# connector_PCI.net
KiCad netlist of a schematic drawn in EAGLE
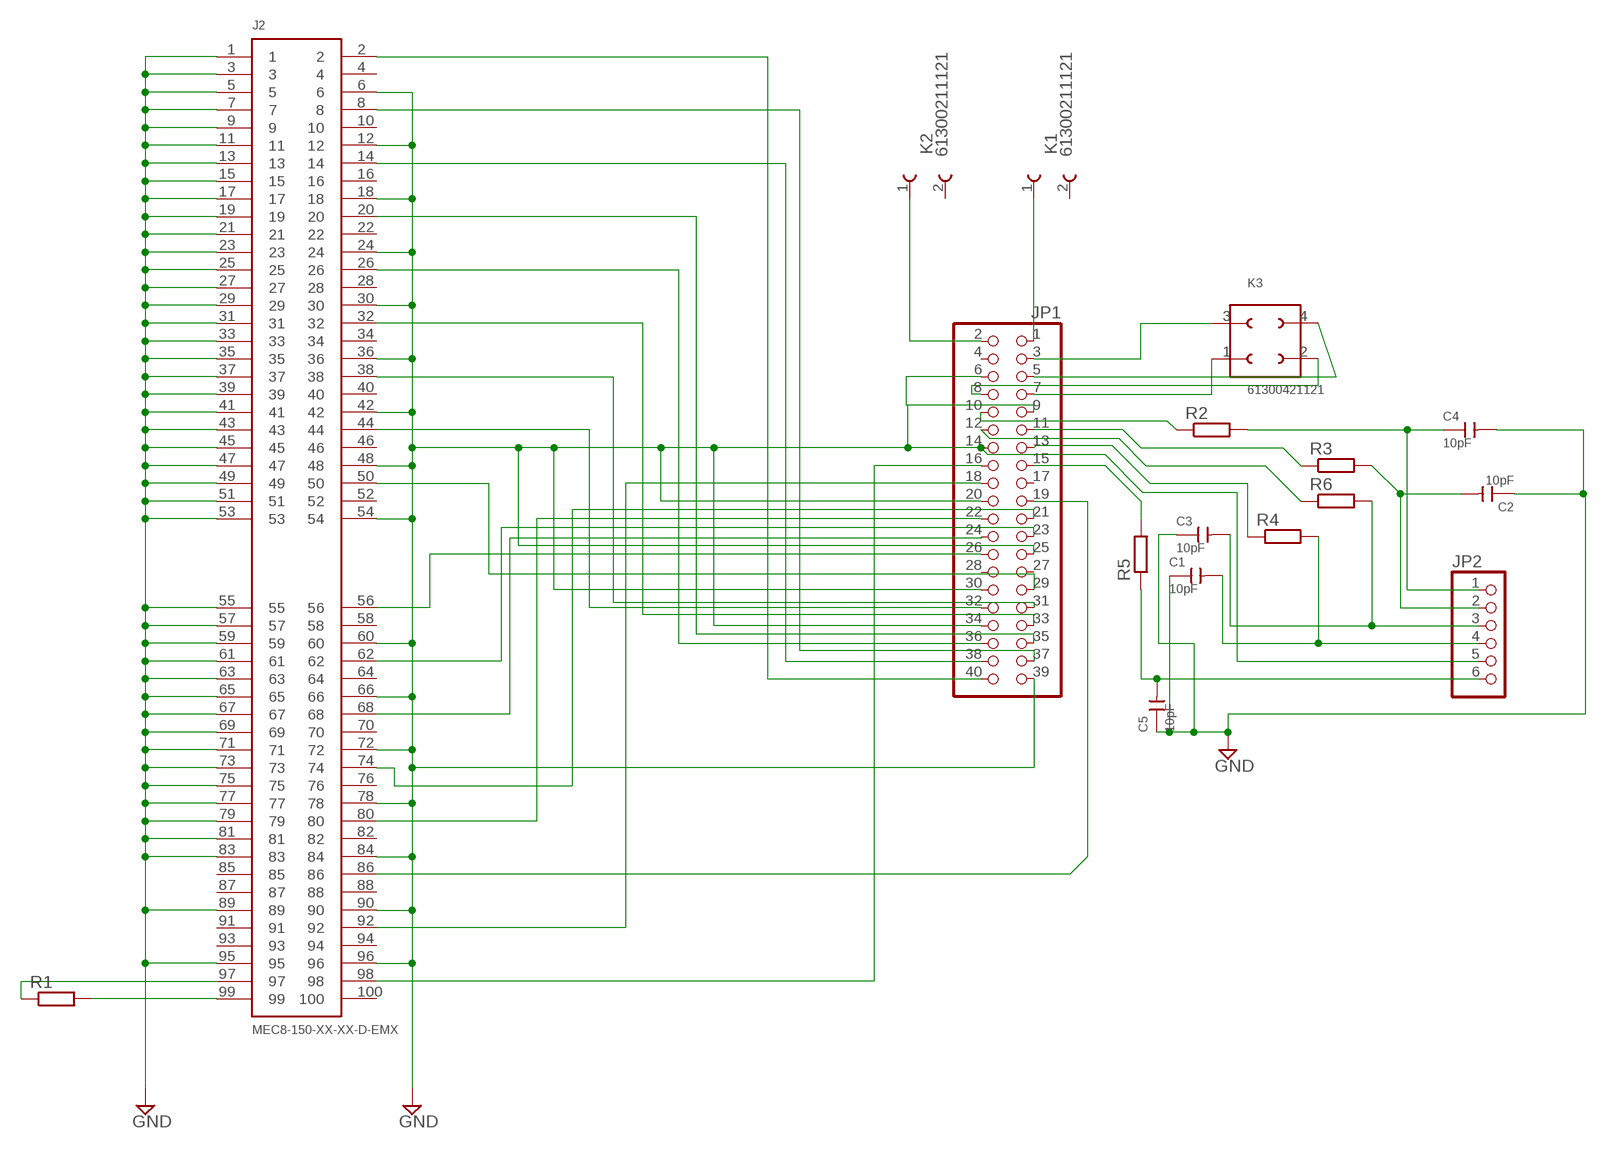
[diagram p0: schematic, sheet 1]

(export (version "E")
  (design (tool "Eeschema 10.0.6"))
  (components
    (comp (ref "C1")
      (value "10pF")
      (footprint "eagle-import:C0603")
      (fields (field (name "MPN") "CC0603KRX7R8BB474"))
      (libsource (lib "eagle-import") (part "CERAMIC-470NF-25V-10%-X7R(0603)"))
    )
    (comp (ref "C2")
      (value "10pF")
      (footprint "eagle-import:C0603")
      (fields (field (name "MPN") "CC0603KRX7R8BB474"))
      (libsource (lib "eagle-import") (part "CERAMIC-470NF-25V-10%-X7R(0603)"))
    )
    (comp (ref "C3")
      (value "10pF")
      (footprint "eagle-import:C0603")
      (fields (field (name "MPN") "CC0603KRX7R8BB474"))
      (libsource (lib "eagle-import") (part "CERAMIC-470NF-25V-10%-X7R(0603)"))
    )
    (comp (ref "C4")
      (value "10pF")
      (footprint "eagle-import:C0603")
      (fields (field (name "MPN") "CC0603KRX7R8BB474"))
      (libsource (lib "eagle-import") (part "CERAMIC-470NF-25V-10%-X7R(0603)"))
    )
    (comp (ref "C5")
      (value "10pF")
      (footprint "eagle-import:C0603")
      (fields (field (name "MPN") "CC0603KRX7R8BB474"))
      (libsource (lib "eagle-import") (part "CERAMIC-470NF-25V-10%-X7R(0603)"))
    )
    (comp (ref "J2")
      (value "MEC8-150-XX-XX-D-EMX")
      (footprint "eagle-import:MEC8-150-XX-XX-D-EMX")
      (libsource (lib "eagle-import") (part "MEC8-150-XX-XX-D-EMX"))
    )
    (comp (ref "JP1")
      (value "PINHD-2X20_2.54")
      (footprint "eagle-import:2X20")
      (libsource (lib "eagle-import") (part "PINHD-2X20_2.54"))
    )
    (comp (ref "JP2")
      (value "PINHD-1X06_2.54")
      (footprint "eagle-import:1X06")
      (libsource (lib "eagle-import") (part "PINHD-1X06_2.54"))
    )
    (comp (ref "K1")
      (value "61300211121")
      (footprint "eagle-import:61300211121")
      (libsource (lib "eagle-import") (part "61300211121"))
    )
    (comp (ref "K2")
      (value "61300211121")
      (footprint "eagle-import:61300211121")
      (libsource (lib "eagle-import") (part "61300211121"))
    )
    (comp (ref "K3")
      (value "61300421121")
      (footprint "eagle-import:61300421121")
      (libsource (lib "eagle-import") (part "61300421121"))
    )
    (comp (ref "R1")
      (value "R-EU_R0402")
      (footprint "eagle-import:R0402")
      (libsource (lib "eagle-import") (part "R-EU_R0402"))
    )
    (comp (ref "R2")
      (value "R-EU_R0402")
      (footprint "eagle-import:R0402")
      (libsource (lib "eagle-import") (part "R-EU_R0402"))
    )
    (comp (ref "R3")
      (value "R-EU_R0402")
      (footprint "eagle-import:R0402")
      (libsource (lib "eagle-import") (part "R-EU_R0402"))
    )
    (comp (ref "R4")
      (value "R-EU_R0402")
      (footprint "eagle-import:R0402")
      (libsource (lib "eagle-import") (part "R-EU_R0402"))
    )
    (comp (ref "R5")
      (value "R-EU_R0402")
      (footprint "eagle-import:R0402")
      (libsource (lib "eagle-import") (part "R-EU_R0402"))
    )
    (comp (ref "R6")
      (value "R-EU_R0402")
      (footprint "eagle-import:R0402")
      (libsource (lib "eagle-import") (part "R-EU_R0402"))
    )
  )
  (nets
    (net (code "1") (name "GND") (class "Default")
      (node (ref "C1") (pin "1") (pinfunction "1_1") (pintype "passive"))
      (node (ref "C2") (pin "1") (pinfunction "1_1") (pintype "passive"))
      (node (ref "C3") (pin "1") (pinfunction "1_1") (pintype "passive"))
      (node (ref "C4") (pin "2") (pinfunction "2_2") (pintype "passive"))
      (node (ref "C5") (pin "1") (pinfunction "1_1") (pintype "passive"))
      (node (ref "J2") (pin "1") (pinfunction "1_1") (pintype "bidirectional"))
      (node (ref "J2") (pin "11") (pinfunction "11_11") (pintype "bidirectional"))
      (node (ref "J2") (pin "12") (pinfunction "12_12") (pintype "bidirectional"))
      (node (ref "J2") (pin "13") (pinfunction "13_13") (pintype "bidirectional"))
      (node (ref "J2") (pin "15") (pinfunction "15_15") (pintype "bidirectional"))
      (node (ref "J2") (pin "17") (pinfunction "17_17") (pintype "bidirectional"))
      (node (ref "J2") (pin "18") (pinfunction "18_18") (pintype "bidirectional"))
      (node (ref "J2") (pin "19") (pinfunction "19_19") (pintype "bidirectional"))
      (node (ref "J2") (pin "21") (pinfunction "21_21") (pintype "bidirectional"))
      (node (ref "J2") (pin "23") (pinfunction "23_23") (pintype "bidirectional"))
      (node (ref "J2") (pin "24") (pinfunction "24_24") (pintype "bidirectional"))
      (node (ref "J2") (pin "25") (pinfunction "25_25") (pintype "bidirectional"))
      (node (ref "J2") (pin "27") (pinfunction "27_27") (pintype "bidirectional"))
      (node (ref "J2") (pin "29") (pinfunction "29_29") (pintype "bidirectional"))
      (node (ref "J2") (pin "3") (pinfunction "3_3") (pintype "bidirectional"))
      (node (ref "J2") (pin "30") (pinfunction "30_30") (pintype "bidirectional"))
      (node (ref "J2") (pin "31") (pinfunction "31_31") (pintype "bidirectional"))
      (node (ref "J2") (pin "33") (pinfunction "33_33") (pintype "bidirectional"))
      (node (ref "J2") (pin "35") (pinfunction "35_35") (pintype "bidirectional"))
      (node (ref "J2") (pin "36") (pinfunction "36_36") (pintype "bidirectional"))
      (node (ref "J2") (pin "37") (pinfunction "37_37") (pintype "bidirectional"))
      (node (ref "J2") (pin "39") (pinfunction "39_39") (pintype "bidirectional"))
      (node (ref "J2") (pin "41") (pinfunction "41_41") (pintype "bidirectional"))
      (node (ref "J2") (pin "42") (pinfunction "42_42") (pintype "bidirectional"))
      (node (ref "J2") (pin "43") (pinfunction "43_43") (pintype "bidirectional"))
      (node (ref "J2") (pin "45") (pinfunction "45_45") (pintype "bidirectional"))
      (node (ref "J2") (pin "47") (pinfunction "47_47") (pintype "bidirectional"))
      (node (ref "J2") (pin "48") (pinfunction "48_48") (pintype "bidirectional"))
      (node (ref "J2") (pin "49") (pinfunction "49_49") (pintype "bidirectional"))
      (node (ref "J2") (pin "5") (pinfunction "5_5") (pintype "bidirectional"))
      (node (ref "J2") (pin "51") (pinfunction "51_51") (pintype "bidirectional"))
      (node (ref "J2") (pin "53") (pinfunction "53_53") (pintype "bidirectional"))
      (node (ref "J2") (pin "54") (pinfunction "54_54") (pintype "bidirectional"))
      (node (ref "J2") (pin "55") (pinfunction "55_55") (pintype "bidirectional"))
      (node (ref "J2") (pin "57") (pinfunction "57_57") (pintype "bidirectional"))
      (node (ref "J2") (pin "59") (pinfunction "59_59") (pintype "bidirectional"))
      (node (ref "J2") (pin "6") (pinfunction "6_6") (pintype "bidirectional"))
      (node (ref "J2") (pin "60") (pinfunction "60_60") (pintype "bidirectional"))
      (node (ref "J2") (pin "61") (pinfunction "61_61") (pintype "bidirectional"))
      (node (ref "J2") (pin "63") (pinfunction "63_63") (pintype "bidirectional"))
      (node (ref "J2") (pin "65") (pinfunction "65_65") (pintype "bidirectional"))
      (node (ref "J2") (pin "66") (pinfunction "66_66") (pintype "bidirectional"))
      (node (ref "J2") (pin "67") (pinfunction "67_67") (pintype "bidirectional"))
      (node (ref "J2") (pin "69") (pinfunction "69_69") (pintype "bidirectional"))
      (node (ref "J2") (pin "7") (pinfunction "7_7") (pintype "bidirectional"))
      (node (ref "J2") (pin "71") (pinfunction "71_71") (pintype "bidirectional"))
      (node (ref "J2") (pin "72") (pinfunction "72_72") (pintype "bidirectional"))
      (node (ref "J2") (pin "73") (pinfunction "73_73") (pintype "bidirectional"))
      (node (ref "J2") (pin "75") (pinfunction "75_75") (pintype "bidirectional"))
      (node (ref "J2") (pin "77") (pinfunction "77_77") (pintype "bidirectional"))
      (node (ref "J2") (pin "78") (pinfunction "78_78") (pintype "bidirectional"))
      (node (ref "J2") (pin "79") (pinfunction "79_79") (pintype "bidirectional"))
      (node (ref "J2") (pin "81") (pinfunction "81_81") (pintype "bidirectional"))
      (node (ref "J2") (pin "83") (pinfunction "83_83") (pintype "bidirectional"))
      (node (ref "J2") (pin "84") (pinfunction "84_84") (pintype "bidirectional"))
      (node (ref "J2") (pin "89") (pinfunction "89_89") (pintype "bidirectional"))
      (node (ref "J2") (pin "9") (pinfunction "9_9") (pintype "bidirectional"))
      (node (ref "J2") (pin "90") (pinfunction "90_90") (pintype "bidirectional"))
      (node (ref "J2") (pin "95") (pinfunction "95_95") (pintype "bidirectional"))
      (node (ref "J2") (pin "96") (pinfunction "96_96") (pintype "bidirectional"))
      (node (ref "JP1") (pin "14") (pinfunction "14_14") (pintype "passive"))
      (node (ref "JP1") (pin "20") (pinfunction "20_20") (pintype "passive"))
      (node (ref "JP1") (pin "25") (pinfunction "25_25") (pintype "passive"))
      (node (ref "JP1") (pin "30") (pinfunction "30_30") (pintype "passive"))
      (node (ref "JP1") (pin "34") (pinfunction "34_34") (pintype "passive"))
      (node (ref "JP1") (pin "39") (pinfunction "39_39") (pintype "passive"))
      (node (ref "JP1") (pin "6") (pinfunction "6_6") (pintype "passive"))
      (node (ref "JP1") (pin "9") (pinfunction "9_9") (pintype "passive"))
      (node (ref "JP2") (pin "5") (pinfunction "5_5") (pintype "passive"))
    )
    (net (code "2") (name "Net-(C1-Pad2)") (class "Default")
      (node (ref "C1") (pin "2") (pinfunction "2_2") (pintype "passive"))
      (node (ref "JP2") (pin "4") (pinfunction "4_4") (pintype "passive"))
      (node (ref "R4") (pin "2") (pinfunction "2_2") (pintype "passive"))
    )
    (net (code "3") (name "Net-(C2-Pad2)") (class "Default")
      (node (ref "C2") (pin "2") (pinfunction "2_2") (pintype "passive"))
      (node (ref "JP2") (pin "2") (pinfunction "2_2") (pintype "passive"))
      (node (ref "R3") (pin "2") (pinfunction "2_2") (pintype "passive"))
    )
    (net (code "4") (name "Net-(C3-Pad2)") (class "Default")
      (node (ref "C3") (pin "2") (pinfunction "2_2") (pintype "passive"))
      (node (ref "JP2") (pin "3") (pinfunction "3_3") (pintype "passive"))
      (node (ref "R6") (pin "2") (pinfunction "2_2") (pintype "passive"))
    )
    (net (code "5") (name "Net-(C4-Pad1)") (class "Default")
      (node (ref "C4") (pin "1") (pinfunction "1_1") (pintype "passive"))
      (node (ref "JP2") (pin "1") (pinfunction "1_1") (pintype "passive"))
      (node (ref "R2") (pin "2") (pinfunction "2_2") (pintype "passive"))
    )
    (net (code "6") (name "Net-(C5-Pad2)") (class "Default")
      (node (ref "C5") (pin "2") (pinfunction "2_2") (pintype "passive"))
      (node (ref "JP2") (pin "6") (pinfunction "6_6") (pintype "passive"))
      (node (ref "R5") (pin "1") (pinfunction "1_1") (pintype "passive"))
    )
    (net (code "7") (name "Net-(J2-Pad2)") (class "Default")
      (node (ref "J2") (pin "2") (pinfunction "2_2") (pintype "bidirectional"))
      (node (ref "JP1") (pin "40") (pinfunction "40_40") (pintype "passive"))
    )
    (net (code "8") (name "Net-(J2-Pad8)") (class "Default")
      (node (ref "J2") (pin "8") (pinfunction "8_8") (pintype "bidirectional"))
      (node (ref "JP1") (pin "37") (pinfunction "37_37") (pintype "passive"))
    )
    (net (code "9") (name "Net-(J2-Pad14)") (class "Default")
      (node (ref "J2") (pin "14") (pinfunction "14_14") (pintype "bidirectional"))
      (node (ref "JP1") (pin "38") (pinfunction "38_38") (pintype "passive"))
    )
    (net (code "10") (name "Net-(J2-Pad20)") (class "Default")
      (node (ref "J2") (pin "20") (pinfunction "20_20") (pintype "bidirectional"))
      (node (ref "JP1") (pin "35") (pinfunction "35_35") (pintype "passive"))
    )
    (net (code "11") (name "Net-(J2-Pad26)") (class "Default")
      (node (ref "J2") (pin "26") (pinfunction "26_26") (pintype "bidirectional"))
      (node (ref "JP1") (pin "36") (pinfunction "36_36") (pintype "passive"))
    )
    (net (code "12") (name "Net-(J2-Pad32)") (class "Default")
      (node (ref "J2") (pin "32") (pinfunction "32_32") (pintype "bidirectional"))
      (node (ref "JP1") (pin "33") (pinfunction "33_33") (pintype "passive"))
    )
    (net (code "13") (name "Net-(J2-Pad38)") (class "Default")
      (node (ref "J2") (pin "38") (pinfunction "38_38") (pintype "bidirectional"))
      (node (ref "JP1") (pin "31") (pinfunction "31_31") (pintype "passive"))
    )
    (net (code "14") (name "Net-(J2-Pad44)") (class "Default")
      (node (ref "J2") (pin "44") (pinfunction "44_44") (pintype "bidirectional"))
      (node (ref "JP1") (pin "32") (pinfunction "32_32") (pintype "passive"))
    )
    (net (code "15") (name "Net-(J2-Pad50)") (class "Default")
      (node (ref "J2") (pin "50") (pinfunction "50_50") (pintype "bidirectional"))
      (node (ref "JP1") (pin "29") (pinfunction "29_29") (pintype "passive"))
    )
    (net (code "16") (name "Net-(J2-Pad56)") (class "Default")
      (node (ref "J2") (pin "56") (pinfunction "56_56") (pintype "bidirectional"))
      (node (ref "JP1") (pin "26") (pinfunction "26_26") (pintype "passive"))
    )
    (net (code "17") (name "Net-(J2-Pad62)") (class "Default")
      (node (ref "J2") (pin "62") (pinfunction "62_62") (pintype "bidirectional"))
      (node (ref "JP1") (pin "23") (pinfunction "23_23") (pintype "passive"))
    )
    (net (code "18") (name "Net-(J2-Pad68)") (class "Default")
      (node (ref "J2") (pin "68") (pinfunction "68_68") (pintype "bidirectional"))
      (node (ref "JP1") (pin "24") (pinfunction "24_24") (pintype "passive"))
    )
    (net (code "19") (name "Net-(J2-Pad74)") (class "Default")
      (node (ref "J2") (pin "74") (pinfunction "74_74") (pintype "bidirectional"))
      (node (ref "JP1") (pin "21") (pinfunction "21_21") (pintype "passive"))
    )
    (net (code "20") (name "Net-(J2-Pad80)") (class "Default")
      (node (ref "J2") (pin "80") (pinfunction "80_80") (pintype "bidirectional"))
      (node (ref "JP1") (pin "22") (pinfunction "22_22") (pintype "passive"))
    )
    (net (code "21") (name "Net-(J2-Pad86)") (class "Default")
      (node (ref "J2") (pin "86") (pinfunction "86_86") (pintype "bidirectional"))
      (node (ref "JP1") (pin "19") (pinfunction "19_19") (pintype "passive"))
    )
    (net (code "22") (name "Net-(J2-Pad92)") (class "Default")
      (node (ref "J2") (pin "92") (pinfunction "92_92") (pintype "bidirectional"))
      (node (ref "JP1") (pin "18") (pinfunction "18_18") (pintype "passive"))
    )
    (net (code "23") (name "Net-(J2-Pad97)") (class "Default")
      (node (ref "J2") (pin "97") (pinfunction "97_97") (pintype "bidirectional"))
      (node (ref "R1") (pin "1") (pinfunction "1_1") (pintype "passive"))
    )
    (net (code "24") (name "Net-(J2-Pad98)") (class "Default")
      (node (ref "J2") (pin "98") (pinfunction "98_98") (pintype "bidirectional"))
      (node (ref "JP1") (pin "16") (pinfunction "16_16") (pintype "passive"))
    )
    (net (code "25") (name "Net-(J2-Pad99)") (class "Default")
      (node (ref "J2") (pin "99") (pinfunction "99_99") (pintype "bidirectional"))
      (node (ref "R1") (pin "2") (pinfunction "2_2") (pintype "passive"))
    )
    (net (code "26") (name "Net-(JP1-Pad1)") (class "Default")
      (node (ref "JP1") (pin "1") (pinfunction "1_1") (pintype "passive"))
      (node (ref "K1") (pin "1") (pinfunction "1_1") (pintype "passive"))
    )
    (net (code "27") (name "Net-(JP1-Pad2)") (class "Default")
      (node (ref "JP1") (pin "2") (pinfunction "2_2") (pintype "passive"))
      (node (ref "K2") (pin "1") (pinfunction "1_1") (pintype "passive"))
    )
    (net (code "28") (name "Net-(JP1-Pad5)") (class "Default")
      (node (ref "JP1") (pin "5") (pinfunction "5_5") (pintype "passive"))
      (node (ref "K3") (pin "4") (pinfunction "4_4") (pintype "passive"))
    )
    (net (code "29") (name "Net-(JP1-Pad10)") (class "Default")
      (node (ref "JP1") (pin "10") (pinfunction "10_10") (pintype "passive"))
      (node (ref "R2") (pin "1") (pinfunction "1_1") (pintype "passive"))
    )
    (net (code "30") (name "Net-(JP1-Pad11)") (class "Default")
      (node (ref "JP1") (pin "11") (pinfunction "11_11") (pintype "passive"))
      (node (ref "R3") (pin "1") (pinfunction "1_1") (pintype "passive"))
    )
    (net (code "31") (name "Net-(JP1-Pad12)") (class "Default")
      (node (ref "JP1") (pin "12") (pinfunction "12_12") (pintype "passive"))
      (node (ref "R6") (pin "1") (pinfunction "1_1") (pintype "passive"))
    )
    (net (code "32") (name "Net-(JP1-Pad13)") (class "Default")
      (node (ref "JP1") (pin "13") (pinfunction "13_13") (pintype "passive"))
      (node (ref "R4") (pin "1") (pinfunction "1_1") (pintype "passive"))
    )
    (net (code "33") (name "Net-(JP1-Pad15)") (class "Default")
      (node (ref "JP1") (pin "15") (pinfunction "15_15") (pintype "passive"))
      (node (ref "R5") (pin "2") (pinfunction "2_2") (pintype "passive"))
    )
    (net (code "34") (name "Net-(K3-1)") (class "Default")
      (node (ref "JP1") (pin "3") (pinfunction "3_3") (pintype "passive"))
      (node (ref "K3") (pin "3") (pinfunction "1_3") (pintype "passive"))
    )
    (net (code "35") (name "Net-(K3-2)") (class "Default")
      (node (ref "JP1") (pin "7") (pinfunction "7_7") (pintype "passive"))
      (node (ref "K3") (pin "1") (pinfunction "2_1") (pintype "passive"))
    )
    (net (code "36") (name "Net-(K3-3)") (class "Default")
      (node (ref "JP1") (pin "8") (pinfunction "8_8") (pintype "passive"))
      (node (ref "K3") (pin "2") (pinfunction "3_2") (pintype "passive"))
    )
    (net (code "37") (name "unconnected-(J2-Pad4)") (class "Default")
      (node (ref "J2") (pin "4") (pinfunction "4_4") (pintype "bidirectional"))
    )
    (net (code "38") (name "unconnected-(J2-Pad10)") (class "Default")
      (node (ref "J2") (pin "10") (pinfunction "10_10") (pintype "bidirectional"))
    )
    (net (code "39") (name "unconnected-(J2-Pad16)") (class "Default")
      (node (ref "J2") (pin "16") (pinfunction "16_16") (pintype "bidirectional"))
    )
    (net (code "40") (name "unconnected-(J2-Pad22)") (class "Default")
      (node (ref "J2") (pin "22") (pinfunction "22_22") (pintype "bidirectional"))
    )
    (net (code "41") (name "unconnected-(J2-Pad28)") (class "Default")
      (node (ref "J2") (pin "28") (pinfunction "28_28") (pintype "bidirectional"))
    )
    (net (code "42") (name "unconnected-(J2-Pad34)") (class "Default")
      (node (ref "J2") (pin "34") (pinfunction "34_34") (pintype "bidirectional"))
    )
    (net (code "43") (name "unconnected-(J2-Pad40)") (class "Default")
      (node (ref "J2") (pin "40") (pinfunction "40_40") (pintype "bidirectional"))
    )
    (net (code "44") (name "unconnected-(J2-Pad46)") (class "Default")
      (node (ref "J2") (pin "46") (pinfunction "46_46") (pintype "bidirectional"))
    )
    (net (code "45") (name "unconnected-(J2-Pad52)") (class "Default")
      (node (ref "J2") (pin "52") (pinfunction "52_52") (pintype "bidirectional"))
    )
    (net (code "46") (name "unconnected-(J2-Pad58)") (class "Default")
      (node (ref "J2") (pin "58") (pinfunction "58_58") (pintype "bidirectional"))
    )
    (net (code "47") (name "unconnected-(J2-Pad64)") (class "Default")
      (node (ref "J2") (pin "64") (pinfunction "64_64") (pintype "bidirectional"))
    )
    (net (code "48") (name "unconnected-(J2-Pad70)") (class "Default")
      (node (ref "J2") (pin "70") (pinfunction "70_70") (pintype "bidirectional"))
    )
    (net (code "49") (name "unconnected-(J2-Pad76)") (class "Default")
      (node (ref "J2") (pin "76") (pinfunction "76_76") (pintype "bidirectional"))
    )
    (net (code "50") (name "unconnected-(J2-Pad82)") (class "Default")
      (node (ref "J2") (pin "82") (pinfunction "82_82") (pintype "bidirectional"))
    )
    (net (code "51") (name "unconnected-(J2-Pad85)") (class "Default")
      (node (ref "J2") (pin "85") (pinfunction "85_85") (pintype "bidirectional"))
    )
    (net (code "52") (name "unconnected-(J2-Pad87)") (class "Default")
      (node (ref "J2") (pin "87") (pinfunction "87_87") (pintype "bidirectional"))
    )
    (net (code "53") (name "unconnected-(J2-Pad88)") (class "Default")
      (node (ref "J2") (pin "88") (pinfunction "88_88") (pintype "bidirectional"))
    )
    (net (code "54") (name "unconnected-(J2-Pad91)") (class "Default")
      (node (ref "J2") (pin "91") (pinfunction "91_91") (pintype "bidirectional"))
    )
    (net (code "55") (name "unconnected-(J2-Pad93)") (class "Default")
      (node (ref "J2") (pin "93") (pinfunction "93_93") (pintype "bidirectional"))
    )
    (net (code "56") (name "unconnected-(J2-Pad94)") (class "Default")
      (node (ref "J2") (pin "94") (pinfunction "94_94") (pintype "bidirectional"))
    )
    (net (code "57") (name "unconnected-(J2-Pad100)") (class "Default")
      (node (ref "J2") (pin "100") (pinfunction "100_100") (pintype "bidirectional"))
    )
    (net (code "58") (name "unconnected-(JP1-Pad4)") (class "Default")
      (node (ref "JP1") (pin "4") (pinfunction "4_4") (pintype "passive"))
    )
    (net (code "59") (name "unconnected-(JP1-Pad17)") (class "Default")
      (node (ref "JP1") (pin "17") (pinfunction "17_17") (pintype "passive"))
    )
    (net (code "60") (name "unconnected-(JP1-Pad27)") (class "Default")
      (node (ref "JP1") (pin "27") (pinfunction "27_27") (pintype "passive"))
    )
    (net (code "61") (name "unconnected-(JP1-Pad28)") (class "Default")
      (node (ref "JP1") (pin "28") (pinfunction "28_28") (pintype "passive"))
    )
    (net (code "62") (name "unconnected-(K1-Pad2)") (class "Default")
      (node (ref "K1") (pin "2") (pinfunction "2_2") (pintype "passive"))
    )
    (net (code "63") (name "unconnected-(K2-Pad2)") (class "Default")
      (node (ref "K2") (pin "2") (pinfunction "2_2") (pintype "passive"))
    )
  )
)
